# Sheet1.net
KiCad netlist of a schematic drawn in Altium Designer
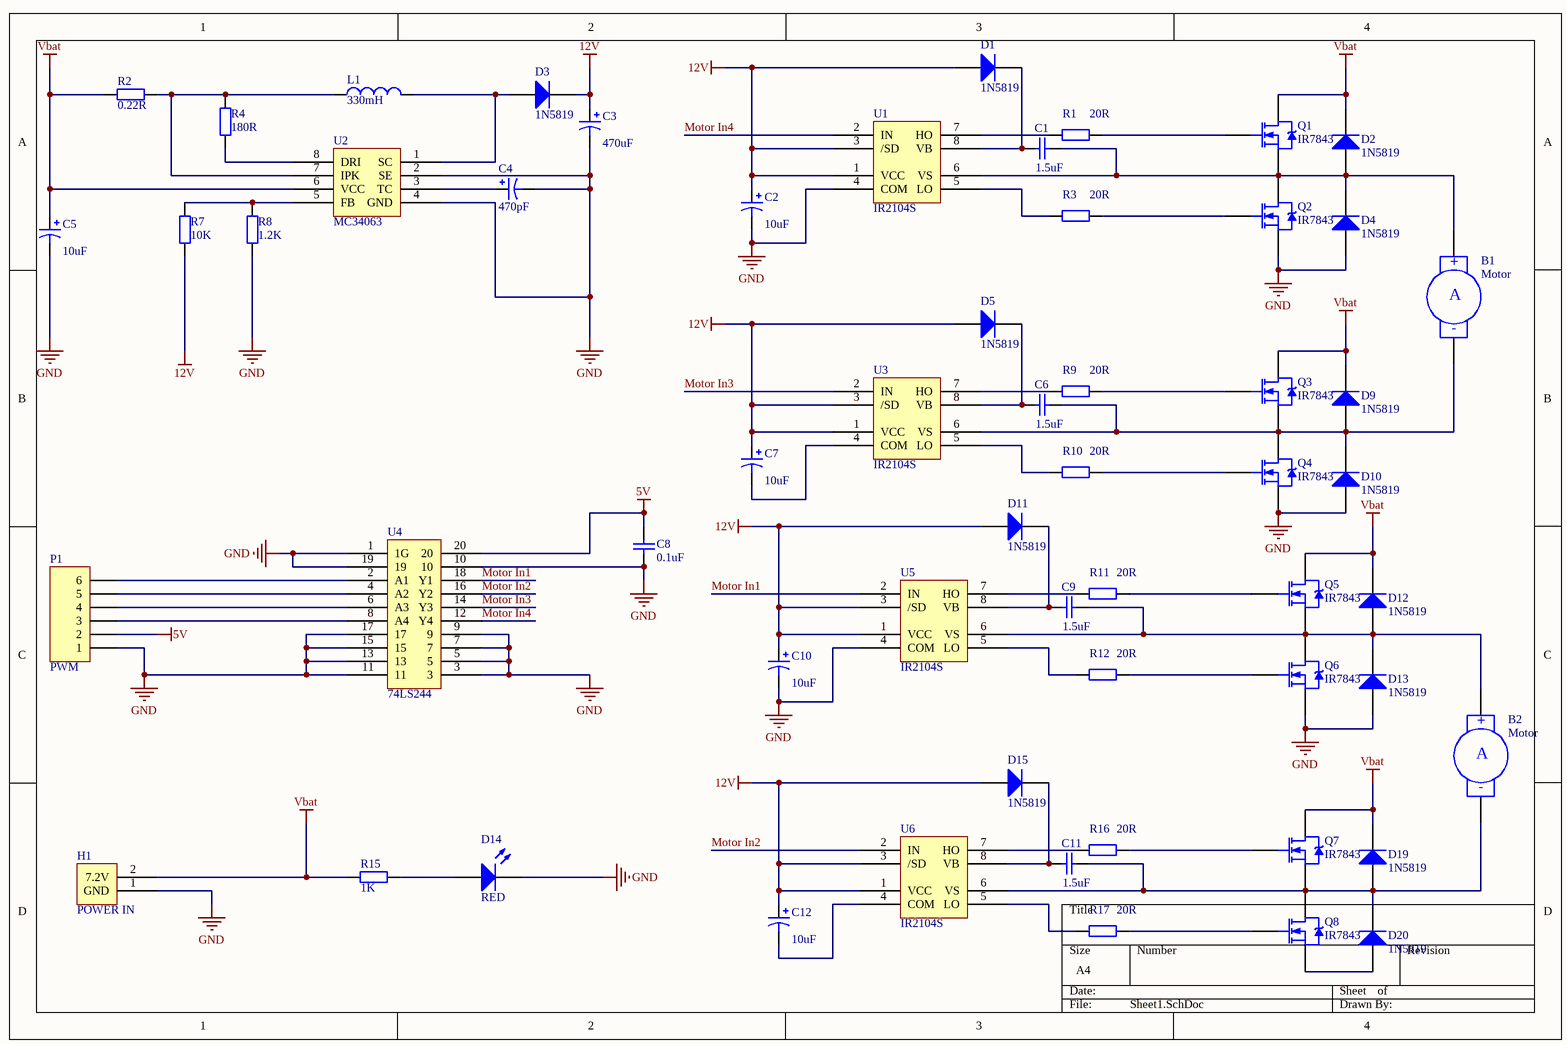
[diagram p0: Sheet1.SchDoc]

(export (version "E")
  (design (tool "Eeschema 10.0.6"))
  (components
    (comp (ref "B1")
      (value "Motor")
      (footprint "KF301-2P")
      (description "Servo Motor")
      (fields (field (name "PUBLISHER") "Altium Limited"))
      (libsource (lib "Miscellaneous Devices") (part "Motor Servo"))
    )
    (comp (ref "B2")
      (value "Motor")
      (footprint "KF301-2P")
      (description "Servo Motor")
      (fields (field (name "PUBLISHER") "Altium Limited"))
      (libsource (lib "Miscellaneous Devices") (part "Motor Servo"))
    )
    (comp (ref "C1")
      (value "1.5uF")
      (footprint "0805(2012)")
      (description "Capacitor")
      (fields (field (name "Comment") "Cap") (field (name "PUBLISHER") "Altium Limited"))
      (libsource (lib "Miscellaneous Devices") (part "Cap"))
    )
    (comp (ref "C2")
      (value "10uF")
      (footprint "SOD-323(0805)")
      (description "Polarized Capacitor (Radial)")
      (fields (field (name "Comment") "Cap Pol1") (field (name "PUBLISHER") "Altium Limited"))
      (libsource (lib "Miscellaneous Devices") (part "Cap Pol1"))
    )
    (comp (ref "C3")
      (value "470uF")
      (footprint "RB5-10.5")
      (description "Polarized Capacitor (Radial)")
      (fields (field (name "Comment") "Cap Pol1") (field (name "PUBLISHER") "Altium Limited"))
      (libsource (lib "Miscellaneous Devices") (part "Cap Pol1"))
    )
    (comp (ref "C4")
      (value "470pF")
      (footprint "SOD-323(0805)")
      (description "Polarized Capacitor (Radial)")
      (fields (field (name "Comment") "Cap Pol1") (field (name "PUBLISHER") "Altium Limited"))
      (libsource (lib "Miscellaneous Devices") (part "Cap Pol1"))
    )
    (comp (ref "C5")
      (value "10uF")
      (footprint "SOD-323(0805)")
      (description "Polarized Capacitor (Radial)")
      (fields (field (name "Comment") "Cap Pol1") (field (name "PUBLISHER") "Altium Limited"))
      (libsource (lib "Miscellaneous Devices") (part "Cap Pol1"))
    )
    (comp (ref "C6")
      (value "1.5uF")
      (footprint "0805(2012)")
      (description "Capacitor")
      (fields (field (name "Comment") "Cap") (field (name "PUBLISHER") "Altium Limited"))
      (libsource (lib "Miscellaneous Devices") (part "Cap"))
    )
    (comp (ref "C7")
      (value "10uF")
      (footprint "SOD-323(0805)")
      (description "Polarized Capacitor (Radial)")
      (fields (field (name "Comment") "Cap Pol1") (field (name "PUBLISHER") "Altium Limited"))
      (libsource (lib "Miscellaneous Devices") (part "Cap Pol1"))
    )
    (comp (ref "C8")
      (value "0.1uF")
      (footprint "0805(2012)")
      (description "Capacitor")
      (fields (field (name "Comment") "Cap") (field (name "PUBLISHER") "Altium Limited"))
      (libsource (lib "LY") (part "Cap"))
    )
    (comp (ref "C9")
      (value "1.5uF")
      (footprint "0805(2012)")
      (description "Capacitor")
      (fields (field (name "Comment") "Cap") (field (name "PUBLISHER") "Altium Limited"))
      (libsource (lib "Miscellaneous Devices") (part "Cap"))
    )
    (comp (ref "C10")
      (value "10uF")
      (footprint "SOD-323(0805)")
      (description "Polarized Capacitor (Radial)")
      (fields (field (name "Comment") "Cap Pol1") (field (name "PUBLISHER") "Altium Limited"))
      (libsource (lib "Miscellaneous Devices") (part "Cap Pol1"))
    )
    (comp (ref "C11")
      (value "1.5uF")
      (footprint "0805(2012)")
      (description "Capacitor")
      (fields (field (name "Comment") "Cap") (field (name "PUBLISHER") "Altium Limited"))
      (libsource (lib "Miscellaneous Devices") (part "Cap"))
    )
    (comp (ref "C12")
      (value "10uF")
      (footprint "SOD-323(0805)")
      (description "Polarized Capacitor (Radial)")
      (fields (field (name "Comment") "Cap Pol1") (field (name "PUBLISHER") "Altium Limited"))
      (libsource (lib "Miscellaneous Devices") (part "Cap Pol1"))
    )
    (comp (ref "D1")
      (value "1N5819")
      (footprint "0805(2012)")
      (description "Silicon Epitaxial Planar Diode for Various Detector, Modulator, Demodulator")
      (fields (field (name "PUBLISHER") "Altium Limited"))
      (libsource (lib "Renesas Diode") (part "1N4148"))
    )
    (comp (ref "D2")
      (value "1N5819")
      (footprint "0805(2012)")
      (description "Silicon Epitaxial Planar Diode for Various Detector, Modulator, Demodulator")
      (fields (field (name "PUBLISHER") "Altium Limited"))
      (libsource (lib "Renesas Diode") (part "1N4148"))
    )
    (comp (ref "D3")
      (value "1N5819")
      (footprint "0805(2012)")
      (description "Silicon Epitaxial Planar Diode for Various Detector, Modulator, Demodulator")
      (fields (field (name "PUBLISHER") "Altium Limited"))
      (libsource (lib "Renesas Diode") (part "1N4148"))
    )
    (comp (ref "D4")
      (value "1N5819")
      (footprint "0805(2012)")
      (description "Silicon Epitaxial Planar Diode for Various Detector, Modulator, Demodulator")
      (fields (field (name "PUBLISHER") "Altium Limited"))
      (libsource (lib "Renesas Diode") (part "1N4148"))
    )
    (comp (ref "D5")
      (value "1N5819")
      (footprint "0805(2012)")
      (description "Silicon Epitaxial Planar Diode for Various Detector, Modulator, Demodulator")
      (fields (field (name "PUBLISHER") "Altium Limited"))
      (libsource (lib "Renesas Diode") (part "1N4148"))
    )
    (comp (ref "D9")
      (value "1N5819")
      (footprint "0805(2012)")
      (description "Silicon Epitaxial Planar Diode for Various Detector, Modulator, Demodulator")
      (fields (field (name "PUBLISHER") "Altium Limited"))
      (libsource (lib "Renesas Diode") (part "1N4148"))
    )
    (comp (ref "D10")
      (value "1N5819")
      (footprint "0805(2012)")
      (description "Silicon Epitaxial Planar Diode for Various Detector, Modulator, Demodulator")
      (fields (field (name "PUBLISHER") "Altium Limited"))
      (libsource (lib "Renesas Diode") (part "1N4148"))
    )
    (comp (ref "D11")
      (value "1N5819")
      (footprint "0805(2012)")
      (description "Silicon Epitaxial Planar Diode for Various Detector, Modulator, Demodulator")
      (fields (field (name "PUBLISHER") "Altium Limited"))
      (libsource (lib "Renesas Diode") (part "1N4148"))
    )
    (comp (ref "D12")
      (value "1N5819")
      (footprint "0805(2012)")
      (description "Silicon Epitaxial Planar Diode for Various Detector, Modulator, Demodulator")
      (fields (field (name "PUBLISHER") "Altium Limited"))
      (libsource (lib "Renesas Diode") (part "1N4148"))
    )
    (comp (ref "D13")
      (value "1N5819")
      (footprint "0805(2012)")
      (description "Silicon Epitaxial Planar Diode for Various Detector, Modulator, Demodulator")
      (fields (field (name "PUBLISHER") "Altium Limited"))
      (libsource (lib "Renesas Diode") (part "1N4148"))
    )
    (comp (ref "D14")
      (value "RED")
      (footprint "0805LED")
      (description "Typical RED, GREEN, YELLOW, AMBER GaAs LED")
      (fields (field (name "PUBLISHER") "Altium Limited"))
      (libsource (lib "LY") (part "LED2"))
    )
    (comp (ref "D15")
      (value "1N5819")
      (footprint "0805(2012)")
      (description "Silicon Epitaxial Planar Diode for Various Detector, Modulator, Demodulator")
      (fields (field (name "PUBLISHER") "Altium Limited"))
      (libsource (lib "Renesas Diode") (part "1N4148"))
    )
    (comp (ref "D19")
      (value "1N5819")
      (footprint "0805(2012)")
      (description "Silicon Epitaxial Planar Diode for Various Detector, Modulator, Demodulator")
      (fields (field (name "PUBLISHER") "Altium Limited"))
      (libsource (lib "Renesas Diode") (part "1N4148"))
    )
    (comp (ref "D20")
      (value "1N5819")
      (footprint "0805(2012)")
      (description "Silicon Epitaxial Planar Diode for Various Detector, Modulator, Demodulator")
      (fields (field (name "PUBLISHER") "Altium Limited"))
      (libsource (lib "Renesas Diode") (part "1N4148"))
    )
    (comp (ref "H1")
      (value "POWER IN")
      (footprint "KF301-2P")
      (libsource (lib "MOS motor") (part "POWER IN"))
    )
    (comp (ref "L1")
      (value "330mH")
      (footprint "电感10*12")
      (description "Inductor")
      (fields (field (name "PUBLISHER") "Altium Limited"))
      (libsource (lib "Miscellaneous Devices") (part "Inductor"))
    )
    (comp (ref "P1")
      (value "PWM")
      (footprint "HDR1X6")
      (description "Header, 6-Pin")
      (fields (field (name "PUBLISHER") "Altium Limited"))
      (libsource (lib "Miscellaneous Connectors") (part "Header 6"))
    )
    (comp (ref "Q1")
      (value "IR7843")
      (footprint "LR7843")
      (description "N-Channel Power MOSFET")
      (fields (field (name "PUBLISHER") "Altium Limited"))
      (libsource (lib "PowerIn") (part "IR7843"))
    )
    (comp (ref "Q2")
      (value "IR7843")
      (footprint "LR7843")
      (description "N-Channel Power MOSFET")
      (fields (field (name "PUBLISHER") "Altium Limited"))
      (libsource (lib "PowerIn") (part "IR7843"))
    )
    (comp (ref "Q3")
      (value "IR7843")
      (footprint "LR7843")
      (description "N-Channel Power MOSFET")
      (fields (field (name "PUBLISHER") "Altium Limited"))
      (libsource (lib "PowerIn") (part "IR7843"))
    )
    (comp (ref "Q4")
      (value "IR7843")
      (footprint "LR7843")
      (description "N-Channel Power MOSFET")
      (fields (field (name "PUBLISHER") "Altium Limited"))
      (libsource (lib "PowerIn") (part "IR7843"))
    )
    (comp (ref "Q5")
      (value "IR7843")
      (footprint "LR7843")
      (description "N-Channel Power MOSFET")
      (fields (field (name "PUBLISHER") "Altium Limited"))
      (libsource (lib "PowerIn") (part "IR7843"))
    )
    (comp (ref "Q6")
      (value "IR7843")
      (footprint "LR7843")
      (description "N-Channel Power MOSFET")
      (fields (field (name "PUBLISHER") "Altium Limited"))
      (libsource (lib "PowerIn") (part "IR7843"))
    )
    (comp (ref "Q7")
      (value "IR7843")
      (footprint "LR7843")
      (description "N-Channel Power MOSFET")
      (fields (field (name "PUBLISHER") "Altium Limited"))
      (libsource (lib "PowerIn") (part "IR7843"))
    )
    (comp (ref "Q8")
      (value "IR7843")
      (footprint "LR7843")
      (description "N-Channel Power MOSFET")
      (fields (field (name "PUBLISHER") "Altium Limited"))
      (libsource (lib "PowerIn") (part "IR7843"))
    )
    (comp (ref "R1")
      (value "20R")
      (footprint "0805(2012)")
      (description "Resistor")
      (fields (field (name "Comment") "Res2") (field (name "PUBLISHER") "Altium Limited"))
      (libsource (lib "altium-import") (part "root_0_Res2_"))
    )
    (comp (ref "R2")
      (value "0.22R")
      (footprint "1206(3216)")
      (description "Resistor")
      (fields (field (name "Comment") "Res2") (field (name "PUBLISHER") "Altium Limited"))
      (libsource (lib "altium-import") (part "root_2_Res2_"))
    )
    (comp (ref "R3")
      (value "20R")
      (footprint "0805(2012)")
      (description "Resistor")
      (fields (field (name "Comment") "Res2") (field (name "PUBLISHER") "Altium Limited"))
      (libsource (lib "altium-import") (part "root_0_Res2_"))
    )
    (comp (ref "R4")
      (value "180R")
      (footprint "0805(2012)")
      (description "Resistor")
      (fields (field (name "Comment") "Res2") (field (name "PUBLISHER") "Altium Limited"))
      (libsource (lib "LY") (part "Res2"))
    )
    (comp (ref "R7")
      (value "10K")
      (footprint "0805(2012)")
      (description "Resistor")
      (fields (field (name "Comment") "Res2") (field (name "PUBLISHER") "Altium Limited"))
      (libsource (lib "LY") (part "Res2"))
    )
    (comp (ref "R8")
      (value "1.2K")
      (footprint "0805(2012)")
      (description "Resistor")
      (fields (field (name "Comment") "Res2") (field (name "PUBLISHER") "Altium Limited"))
      (libsource (lib "LY") (part "Res2"))
    )
    (comp (ref "R9")
      (value "20R")
      (footprint "0805(2012)")
      (description "Resistor")
      (fields (field (name "Comment") "Res2") (field (name "PUBLISHER") "Altium Limited"))
      (libsource (lib "altium-import") (part "root_0_Res2_"))
    )
    (comp (ref "R10")
      (value "20R")
      (footprint "0805(2012)")
      (description "Resistor")
      (fields (field (name "Comment") "Res2") (field (name "PUBLISHER") "Altium Limited"))
      (libsource (lib "altium-import") (part "root_0_Res2_"))
    )
    (comp (ref "R11")
      (value "20R")
      (footprint "0805(2012)")
      (description "Resistor")
      (fields (field (name "Comment") "Res2") (field (name "PUBLISHER") "Altium Limited"))
      (libsource (lib "altium-import") (part "root_0_Res2_"))
    )
    (comp (ref "R12")
      (value "20R")
      (footprint "0805(2012)")
      (description "Resistor")
      (fields (field (name "Comment") "Res2") (field (name "PUBLISHER") "Altium Limited"))
      (libsource (lib "altium-import") (part "root_0_Res2_"))
    )
    (comp (ref "R15")
      (value "1K")
      (footprint "0805(2012)")
      (description "Resistor")
      (fields (field (name "Comment") "Res2") (field (name "PUBLISHER") "Altium Limited"))
      (libsource (lib "") (part "Res2_1"))
    )
    (comp (ref "R16")
      (value "20R")
      (footprint "0805(2012)")
      (description "Resistor")
      (fields (field (name "Comment") "Res2") (field (name "PUBLISHER") "Altium Limited"))
      (libsource (lib "altium-import") (part "root_0_Res2_"))
    )
    (comp (ref "R17")
      (value "20R")
      (footprint "0805(2012)")
      (description "Resistor")
      (fields (field (name "Comment") "Res2") (field (name "PUBLISHER") "Altium Limited"))
      (libsource (lib "altium-import") (part "root_0_Res2_"))
    )
    (comp (ref "U1") (value "IR2104S") (footprint "IR2104S") (libsource (lib "LY") (part "IR2104S")))
    (comp (ref "U2") (value "MC34063") (footprint "MC34063") (libsource (lib "LY") (part "MC34063")))
    (comp (ref "U3") (value "IR2104S") (footprint "IR2104S") (libsource (lib "LY") (part "IR2104S")))
    (comp (ref "U4") (value "74LS244") (footprint "74ls244DA") (libsource (lib "LY") (part "74LS244")))
    (comp (ref "U5") (value "IR2104S") (footprint "IR2104S") (libsource (lib "LY") (part "IR2104S")))
    (comp (ref "U6") (value "IR2104S") (footprint "IR2104S") (libsource (lib "LY") (part "IR2104S")))
  )
  (nets
    (net (code "1") (name "/Motor In1") (class "Default")
      (node (ref "U4") (pin "18") (pinfunction "Y1_18") (pintype "passive"))
      (node (ref "U5") (pin "2") (pinfunction "IN_2") (pintype "passive"))
    )
    (net (code "2") (name "/Motor In2") (class "Default")
      (node (ref "U4") (pin "16") (pinfunction "Y2_16") (pintype "passive"))
      (node (ref "U6") (pin "2") (pinfunction "IN_2") (pintype "passive"))
    )
    (net (code "3") (name "/Motor In3") (class "Default")
      (node (ref "U3") (pin "2") (pinfunction "IN_2") (pintype "passive"))
      (node (ref "U4") (pin "14") (pinfunction "Y3_14") (pintype "passive"))
    )
    (net (code "4") (name "/Motor In4") (class "Default")
      (node (ref "U1") (pin "2") (pinfunction "IN_2") (pintype "passive"))
      (node (ref "U4") (pin "12") (pinfunction "Y4_12") (pintype "passive"))
    )
    (net (code "5") (name "5V") (class "Default")
      (node (ref "C8") (pin "2") (pinfunction "2_2") (pintype "passive"))
      (node (ref "P1") (pin "2") (pinfunction "2_2") (pintype "passive"))
      (node (ref "U4") (pin "20") (pinfunction "20_20") (pintype "passive"))
    )
    (net (code "6") (name "12V") (class "Default")
      (node (ref "C10") (pin "1") (pinfunction "1_1") (pintype "passive"))
      (node (ref "C12") (pin "1") (pinfunction "1_1") (pintype "passive"))
      (node (ref "C2") (pin "1") (pinfunction "1_1") (pintype "passive"))
      (node (ref "C3") (pin "1") (pinfunction "1_1") (pintype "passive"))
      (node (ref "C7") (pin "1") (pinfunction "1_1") (pintype "passive"))
      (node (ref "D1") (pin "2") (pinfunction "A_2") (pintype "passive"))
      (node (ref "D11") (pin "2") (pinfunction "A_2") (pintype "passive"))
      (node (ref "D15") (pin "2") (pinfunction "A_2") (pintype "passive"))
      (node (ref "D3") (pin "1") (pinfunction "K_1") (pintype "passive"))
      (node (ref "D5") (pin "2") (pinfunction "A_2") (pintype "passive"))
      (node (ref "R7") (pin "1") (pinfunction "1_1") (pintype "passive"))
      (node (ref "U1") (pin "1") (pinfunction "VCC_1") (pintype "passive"))
      (node (ref "U1") (pin "3") (pinfunction "/SD_3") (pintype "passive"))
      (node (ref "U3") (pin "1") (pinfunction "VCC_1") (pintype "passive"))
      (node (ref "U3") (pin "3") (pinfunction "/SD_3") (pintype "passive"))
      (node (ref "U5") (pin "1") (pinfunction "VCC_1") (pintype "passive"))
      (node (ref "U5") (pin "3") (pinfunction "/SD_3") (pintype "passive"))
      (node (ref "U6") (pin "1") (pinfunction "VCC_1") (pintype "passive"))
      (node (ref "U6") (pin "3") (pinfunction "/SD_3") (pintype "passive"))
    )
    (net (code "7") (name "GND") (class "Default")
      (node (ref "C10") (pin "2") (pinfunction "2_2") (pintype "passive"))
      (node (ref "C2") (pin "2") (pinfunction "2_2") (pintype "passive"))
      (node (ref "C3") (pin "2") (pinfunction "2_2") (pintype "passive"))
      (node (ref "C4") (pin "2") (pinfunction "2_2") (pintype "passive"))
      (node (ref "C5") (pin "2") (pinfunction "2_2") (pintype "passive"))
      (node (ref "C8") (pin "1") (pinfunction "1_1") (pintype "passive"))
      (node (ref "D10") (pin "2") (pinfunction "A_2") (pintype "passive"))
      (node (ref "D13") (pin "2") (pinfunction "A_2") (pintype "passive"))
      (node (ref "D14") (pin "2") (pinfunction "K_2") (pintype "passive"))
      (node (ref "D4") (pin "2") (pinfunction "A_2") (pintype "passive"))
      (node (ref "H1") (pin "1") (pinfunction "GND_1") (pintype "passive"))
      (node (ref "P1") (pin "1") (pinfunction "1_1") (pintype "passive"))
      (node (ref "Q2") (pin "3") (pinfunction "S_3") (pintype "passive"))
      (node (ref "Q4") (pin "3") (pinfunction "S_3") (pintype "passive"))
      (node (ref "Q6") (pin "3") (pinfunction "S_3") (pintype "passive"))
      (node (ref "R8") (pin "1") (pinfunction "1_1") (pintype "passive"))
      (node (ref "U1") (pin "4") (pinfunction "COM_4") (pintype "passive"))
      (node (ref "U2") (pin "2") (pinfunction "SE_2") (pintype "passive"))
      (node (ref "U2") (pin "4") (pinfunction "GND_4") (pintype "passive"))
      (node (ref "U4") (pin "1") (pinfunction "1G_1") (pintype "passive"))
      (node (ref "U4") (pin "10") (pinfunction "10_10") (pintype "passive"))
      (node (ref "U4") (pin "11") (pinfunction "11_11") (pintype "passive"))
      (node (ref "U4") (pin "13") (pinfunction "13_13") (pintype "passive"))
      (node (ref "U4") (pin "15") (pinfunction "15_15") (pintype "passive"))
      (node (ref "U4") (pin "17") (pinfunction "17_17") (pintype "passive"))
      (node (ref "U4") (pin "19") (pinfunction "19_19") (pintype "passive"))
      (node (ref "U4") (pin "3") (pinfunction "3_3") (pintype "passive"))
      (node (ref "U4") (pin "5") (pinfunction "5_5") (pintype "passive"))
      (node (ref "U4") (pin "7") (pinfunction "7_7") (pintype "passive"))
      (node (ref "U4") (pin "9") (pinfunction "9_9") (pintype "passive"))
      (node (ref "U5") (pin "4") (pinfunction "COM_4") (pintype "passive"))
    )
    (net (code "8") (name "Net-(B1-+)") (class "Default")
      (node (ref "B1") (pin "1") (pinfunction "+_1") (pintype "passive"))
      (node (ref "C1") (pin "2") (pinfunction "2_2") (pintype "passive"))
      (node (ref "D2") (pin "2") (pinfunction "A_2") (pintype "passive"))
      (node (ref "D4") (pin "1") (pinfunction "K_1") (pintype "passive"))
      (node (ref "Q1") (pin "3") (pinfunction "S_3") (pintype "passive"))
      (node (ref "Q2") (pin "2") (pinfunction "D_2") (pintype "passive"))
      (node (ref "U1") (pin "6") (pinfunction "VS_6") (pintype "passive"))
    )
    (net (code "9") (name "Net-(B1--)") (class "Default")
      (node (ref "B1") (pin "2") (pinfunction "-_2") (pintype "passive"))
      (node (ref "C6") (pin "2") (pinfunction "2_2") (pintype "passive"))
      (node (ref "D10") (pin "1") (pinfunction "K_1") (pintype "passive"))
      (node (ref "D9") (pin "2") (pinfunction "A_2") (pintype "passive"))
      (node (ref "Q3") (pin "3") (pinfunction "S_3") (pintype "passive"))
      (node (ref "Q4") (pin "2") (pinfunction "D_2") (pintype "passive"))
      (node (ref "U3") (pin "6") (pinfunction "VS_6") (pintype "passive"))
    )
    (net (code "10") (name "Net-(B2-+)") (class "Default")
      (node (ref "B2") (pin "1") (pinfunction "+_1") (pintype "passive"))
      (node (ref "C9") (pin "2") (pinfunction "2_2") (pintype "passive"))
      (node (ref "D12") (pin "2") (pinfunction "A_2") (pintype "passive"))
      (node (ref "D13") (pin "1") (pinfunction "K_1") (pintype "passive"))
      (node (ref "Q5") (pin "3") (pinfunction "S_3") (pintype "passive"))
      (node (ref "Q6") (pin "2") (pinfunction "D_2") (pintype "passive"))
      (node (ref "U5") (pin "6") (pinfunction "VS_6") (pintype "passive"))
    )
    (net (code "11") (name "Net-(B2--)") (class "Default")
      (node (ref "B2") (pin "2") (pinfunction "-_2") (pintype "passive"))
      (node (ref "C11") (pin "2") (pinfunction "2_2") (pintype "passive"))
      (node (ref "D19") (pin "2") (pinfunction "A_2") (pintype "passive"))
      (node (ref "D20") (pin "1") (pinfunction "K_1") (pintype "passive"))
      (node (ref "Q7") (pin "3") (pinfunction "S_3") (pintype "passive"))
      (node (ref "Q8") (pin "2") (pinfunction "D_2") (pintype "passive"))
      (node (ref "U6") (pin "6") (pinfunction "VS_6") (pintype "passive"))
    )
    (net (code "12") (name "Net-(D1-K)") (class "Default")
      (node (ref "C1") (pin "1") (pinfunction "1_1") (pintype "passive"))
      (node (ref "D1") (pin "1") (pinfunction "K_1") (pintype "passive"))
      (node (ref "U1") (pin "8") (pinfunction "VB_8") (pintype "passive"))
    )
    (net (code "13") (name "Net-(D3-A)") (class "Default")
      (node (ref "D3") (pin "2") (pinfunction "A_2") (pintype "passive"))
      (node (ref "L1") (pin "2") (pinfunction "2_2") (pintype "passive"))
      (node (ref "U2") (pin "1") (pinfunction "SC_1") (pintype "passive"))
    )
    (net (code "14") (name "Net-(D5-K)") (class "Default")
      (node (ref "C6") (pin "1") (pinfunction "1_1") (pintype "passive"))
      (node (ref "D5") (pin "1") (pinfunction "K_1") (pintype "passive"))
      (node (ref "U3") (pin "8") (pinfunction "VB_8") (pintype "passive"))
    )
    (net (code "15") (name "Net-(D11-K)") (class "Default")
      (node (ref "C9") (pin "1") (pinfunction "1_1") (pintype "passive"))
      (node (ref "D11") (pin "1") (pinfunction "K_1") (pintype "passive"))
      (node (ref "U5") (pin "8") (pinfunction "VB_8") (pintype "passive"))
    )
    (net (code "16") (name "Net-(D14-A)") (class "Default")
      (node (ref "D14") (pin "1") (pinfunction "A_1") (pintype "passive"))
      (node (ref "R15") (pin "2") (pinfunction "2_2") (pintype "passive"))
    )
    (net (code "17") (name "Net-(D15-K)") (class "Default")
      (node (ref "C11") (pin "1") (pinfunction "1_1") (pintype "passive"))
      (node (ref "D15") (pin "1") (pinfunction "K_1") (pintype "passive"))
      (node (ref "U6") (pin "8") (pinfunction "VB_8") (pintype "passive"))
    )
    (net (code "18") (name "Net-(D20-A)") (class "Default")
      (node (ref "D20") (pin "2") (pinfunction "A_2") (pintype "passive"))
      (node (ref "Q8") (pin "3") (pinfunction "S_3") (pintype "passive"))
    )
    (net (code "19") (name "Net-(Q1-G)") (class "Default")
      (node (ref "Q1") (pin "1") (pinfunction "G_1") (pintype "passive"))
      (node (ref "R1") (pin "2") (pinfunction "2_2") (pintype "passive"))
    )
    (net (code "20") (name "Net-(Q2-G)") (class "Default")
      (node (ref "Q2") (pin "1") (pinfunction "G_1") (pintype "passive"))
      (node (ref "R3") (pin "2") (pinfunction "2_2") (pintype "passive"))
    )
    (net (code "21") (name "Net-(Q3-G)") (class "Default")
      (node (ref "Q3") (pin "1") (pinfunction "G_1") (pintype "passive"))
      (node (ref "R9") (pin "2") (pinfunction "2_2") (pintype "passive"))
    )
    (net (code "22") (name "Net-(Q4-G)") (class "Default")
      (node (ref "Q4") (pin "1") (pinfunction "G_1") (pintype "passive"))
      (node (ref "R10") (pin "2") (pinfunction "2_2") (pintype "passive"))
    )
    (net (code "23") (name "Net-(Q5-G)") (class "Default")
      (node (ref "Q5") (pin "1") (pinfunction "G_1") (pintype "passive"))
      (node (ref "R11") (pin "2") (pinfunction "2_2") (pintype "passive"))
    )
    (net (code "24") (name "Net-(Q6-G)") (class "Default")
      (node (ref "Q6") (pin "1") (pinfunction "G_1") (pintype "passive"))
      (node (ref "R12") (pin "2") (pinfunction "2_2") (pintype "passive"))
    )
    (net (code "25") (name "Net-(Q7-G)") (class "Default")
      (node (ref "Q7") (pin "1") (pinfunction "G_1") (pintype "passive"))
      (node (ref "R16") (pin "2") (pinfunction "2_2") (pintype "passive"))
    )
    (net (code "26") (name "Net-(Q8-G)") (class "Default")
      (node (ref "Q8") (pin "1") (pinfunction "G_1") (pintype "passive"))
      (node (ref "R17") (pin "2") (pinfunction "2_2") (pintype "passive"))
    )
    (net (code "27") (name "Net-(U1-HO)") (class "Default")
      (node (ref "R1") (pin "1") (pinfunction "1_1") (pintype "passive"))
      (node (ref "U1") (pin "7") (pinfunction "HO_7") (pintype "passive"))
    )
    (net (code "28") (name "Net-(U1-LO)") (class "Default")
      (node (ref "R3") (pin "1") (pinfunction "1_1") (pintype "passive"))
      (node (ref "U1") (pin "5") (pinfunction "LO_5") (pintype "passive"))
    )
    (net (code "29") (name "Net-(U2-DRI)") (class "Default")
      (node (ref "R4") (pin "1") (pinfunction "1_1") (pintype "passive"))
      (node (ref "U2") (pin "8") (pinfunction "DRI_8") (pintype "passive"))
    )
    (net (code "30") (name "Net-(U2-FB)") (class "Default")
      (node (ref "R7") (pin "2") (pinfunction "2_2") (pintype "passive"))
      (node (ref "R8") (pin "2") (pinfunction "2_2") (pintype "passive"))
      (node (ref "U2") (pin "5") (pinfunction "FB_5") (pintype "passive"))
    )
    (net (code "31") (name "Net-(U2-IPK)") (class "Default")
      (node (ref "L1") (pin "1") (pinfunction "1_1") (pintype "passive"))
      (node (ref "R2") (pin "1") (pinfunction "1_1") (pintype "passive"))
      (node (ref "R4") (pin "2") (pinfunction "2_2") (pintype "passive"))
      (node (ref "U2") (pin "7") (pinfunction "IPK_7") (pintype "passive"))
    )
    (net (code "32") (name "Net-(U2-TC)") (class "Default")
      (node (ref "C4") (pin "1") (pinfunction "1_1") (pintype "passive"))
      (node (ref "U2") (pin "3") (pinfunction "TC_3") (pintype "passive"))
    )
    (net (code "33") (name "Net-(U3-COM)") (class "Default")
      (node (ref "C7") (pin "2") (pinfunction "2_2") (pintype "passive"))
      (node (ref "U3") (pin "4") (pinfunction "COM_4") (pintype "passive"))
    )
    (net (code "34") (name "Net-(U3-HO)") (class "Default")
      (node (ref "R9") (pin "1") (pinfunction "1_1") (pintype "passive"))
      (node (ref "U3") (pin "7") (pinfunction "HO_7") (pintype "passive"))
    )
    (net (code "35") (name "Net-(U3-LO)") (class "Default")
      (node (ref "R10") (pin "1") (pinfunction "1_1") (pintype "passive"))
      (node (ref "U3") (pin "5") (pinfunction "LO_5") (pintype "passive"))
    )
    (net (code "36") (name "Net-(U4-A1)") (class "Default")
      (node (ref "P1") (pin "6") (pinfunction "6_6") (pintype "passive"))
      (node (ref "U4") (pin "2") (pinfunction "A1_2") (pintype "passive"))
    )
    (net (code "37") (name "Net-(U4-A2)") (class "Default")
      (node (ref "P1") (pin "5") (pinfunction "5_5") (pintype "passive"))
      (node (ref "U4") (pin "4") (pinfunction "A2_4") (pintype "passive"))
    )
    (net (code "38") (name "Net-(U4-A3)") (class "Default")
      (node (ref "P1") (pin "4") (pinfunction "4_4") (pintype "passive"))
      (node (ref "U4") (pin "6") (pinfunction "A3_6") (pintype "passive"))
    )
    (net (code "39") (name "Net-(U4-A4)") (class "Default")
      (node (ref "P1") (pin "3") (pinfunction "3_3") (pintype "passive"))
      (node (ref "U4") (pin "8") (pinfunction "A4_8") (pintype "passive"))
    )
    (net (code "40") (name "Net-(U5-HO)") (class "Default")
      (node (ref "R11") (pin "1") (pinfunction "1_1") (pintype "passive"))
      (node (ref "U5") (pin "7") (pinfunction "HO_7") (pintype "passive"))
    )
    (net (code "41") (name "Net-(U5-LO)") (class "Default")
      (node (ref "R12") (pin "1") (pinfunction "1_1") (pintype "passive"))
      (node (ref "U5") (pin "5") (pinfunction "LO_5") (pintype "passive"))
    )
    (net (code "42") (name "Net-(U6-COM)") (class "Default")
      (node (ref "C12") (pin "2") (pinfunction "2_2") (pintype "passive"))
      (node (ref "U6") (pin "4") (pinfunction "COM_4") (pintype "passive"))
    )
    (net (code "43") (name "Net-(U6-HO)") (class "Default")
      (node (ref "R16") (pin "1") (pinfunction "1_1") (pintype "passive"))
      (node (ref "U6") (pin "7") (pinfunction "HO_7") (pintype "passive"))
    )
    (net (code "44") (name "Net-(U6-LO)") (class "Default")
      (node (ref "R17") (pin "1") (pinfunction "1_1") (pintype "passive"))
      (node (ref "U6") (pin "5") (pinfunction "LO_5") (pintype "passive"))
    )
    (net (code "45") (name "Vbat") (class "Default")
      (node (ref "C5") (pin "1") (pinfunction "1_1") (pintype "passive"))
      (node (ref "D12") (pin "1") (pinfunction "K_1") (pintype "passive"))
      (node (ref "D19") (pin "1") (pinfunction "K_1") (pintype "passive"))
      (node (ref "D2") (pin "1") (pinfunction "K_1") (pintype "passive"))
      (node (ref "D9") (pin "1") (pinfunction "K_1") (pintype "passive"))
      (node (ref "H1") (pin "2") (pinfunction "7.2V_2") (pintype "passive"))
      (node (ref "Q1") (pin "2") (pinfunction "D_2") (pintype "passive"))
      (node (ref "Q3") (pin "2") (pinfunction "D_2") (pintype "passive"))
      (node (ref "Q5") (pin "2") (pinfunction "D_2") (pintype "passive"))
      (node (ref "Q7") (pin "2") (pinfunction "D_2") (pintype "passive"))
      (node (ref "R15") (pin "1") (pinfunction "1_1") (pintype "passive"))
      (node (ref "R2") (pin "2") (pinfunction "2_2") (pintype "passive"))
      (node (ref "U2") (pin "6") (pinfunction "VCC_6") (pintype "passive"))
    )
  )
)
